# Embedded_System_Top.net
KiCad netlist of a schematic drawn in Altium Designer
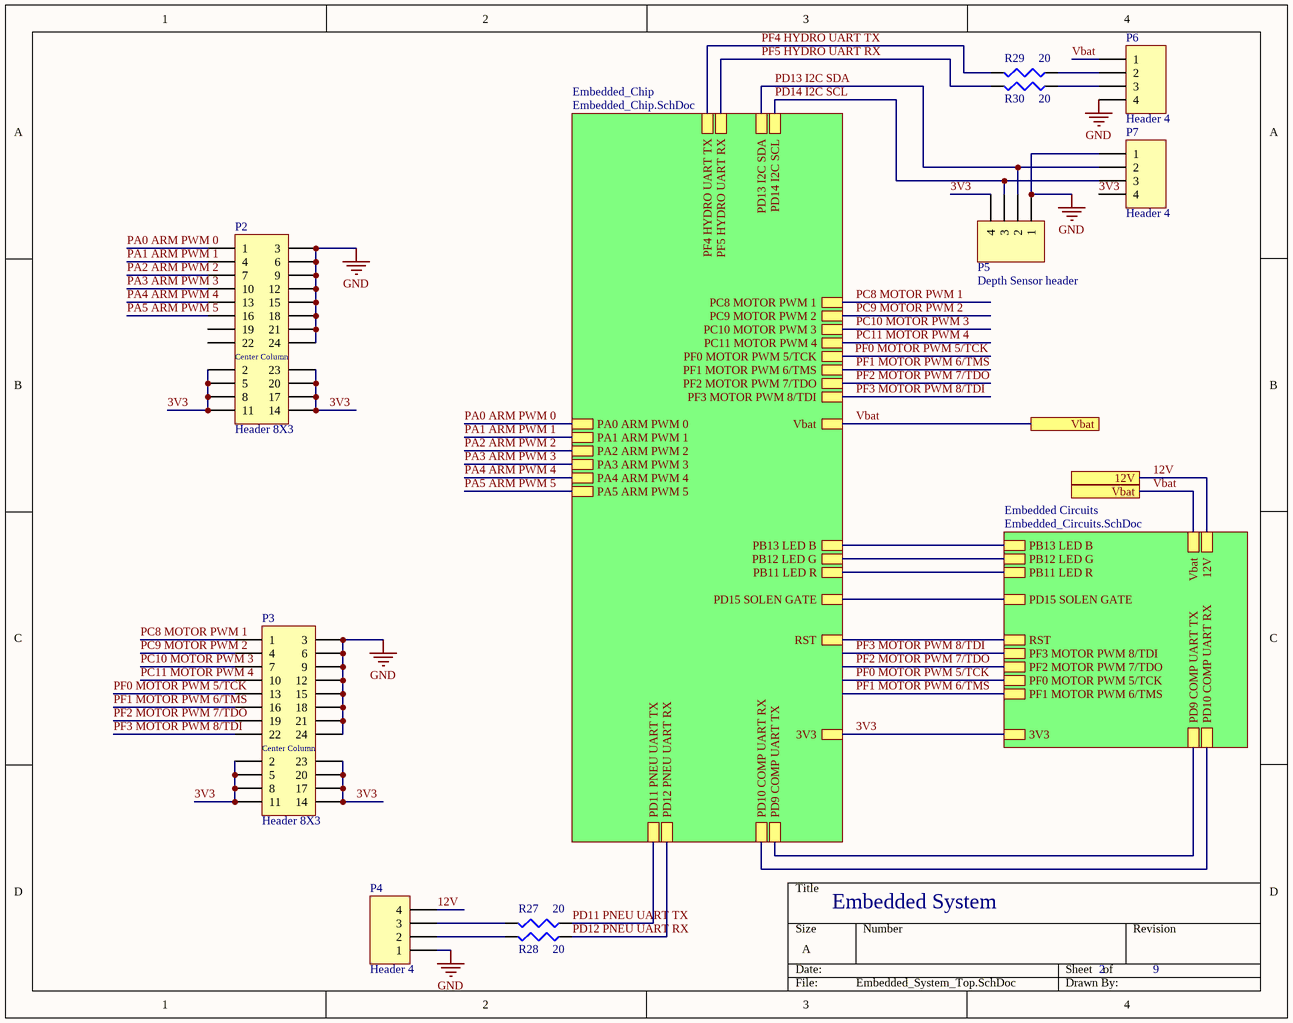
[diagram p0: Embedded_System_Top.SchDoc]

(export (version "E")
  (design (tool "Eeschema 10.0.6"))
  (components
    (comp (ref "P2")
      (value "Header 8X3")
      (footprint "Header 8X3")
      (description "Connector Header Through Hole 24 position 0.079\" (2.00mm)")
      (libsource (lib "Power_Embedded_Board_Library") (part "Header 8X3 (2mm)"))
    )
    (comp (ref "P3")
      (value "Header 8X3")
      (footprint "Header 8X3")
      (description "Connector Header Through Hole 24 position 0.079\" (2.00mm)")
      (libsource (lib "Power_Embedded_Board_Library") (part "Header 8X3 (2mm)"))
    )
    (comp (ref "P4")
      (value "Header 4")
      (footprint "Header 1x4")
      (description "Header, 4-Pin")
      (fields (field (name "PUBLISHER") "Altium Limited"))
      (libsource (lib "") (part "Header 4_2"))
    )
    (comp (ref "P5")
      (value "Depth Sensor header")
      (footprint "DF13-4P-1.25DSA")
      (description "Header, 4-Pin")
      (fields (field (name "PUBLISHER") "Altium Limited"))
      (libsource (lib "") (part "Header 4_1"))
    )
    (comp (ref "P6")
      (value "Header 4")
      (footprint "Header 1x4")
      (description "Header, 4-Pin")
      (fields (field (name "PUBLISHER") "Altium Limited"))
      (libsource (lib "Miscellaneous Connectors") (part "Header 4"))
    )
    (comp (ref "P7")
      (value "Header 4")
      (footprint "DF13-4P-1.25DSA")
      (description "Header, 4-Pin")
      (fields (field (name "PUBLISHER") "Altium Limited"))
      (libsource (lib "Miscellaneous Connectors") (part "Header 4"))
    )
    (comp (ref "R27")
      (value "20")
      (footprint "J1-0603")
      (description "Resistor")
      (fields (field (name "Comment") "Res3") (field (name "PUBLISHER") "Altium Limited"))
      (libsource (lib "Miscellaneous Devices") (part "Res3"))
    )
    (comp (ref "R28")
      (value "20")
      (footprint "J1-0603")
      (description "Resistor")
      (fields (field (name "Comment") "Res3") (field (name "PUBLISHER") "Altium Limited"))
      (libsource (lib "Miscellaneous Devices") (part "Res3"))
    )
    (comp (ref "R29")
      (value "20")
      (footprint "J1-0603")
      (description "Resistor")
      (fields (field (name "Comment") "Res3") (field (name "PUBLISHER") "Altium Limited"))
      (libsource (lib "Miscellaneous Devices") (part "Res3"))
    )
    (comp (ref "R30")
      (value "20")
      (footprint "J1-0603")
      (description "Resistor")
      (fields (field (name "Comment") "Res3") (field (name "PUBLISHER") "Altium Limited"))
      (libsource (lib "Miscellaneous Devices") (part "Res3"))
    )
  )
  (nets
    (net (code "1") (name "/3V3") (class "Default")
      (node (ref "P2") (pin "11") (pinfunction "11_11") (pintype "passive"))
      (node (ref "P2") (pin "14") (pinfunction "14_14") (pintype "passive"))
      (node (ref "P2") (pin "17") (pinfunction "17_17") (pintype "passive"))
      (node (ref "P2") (pin "2") (pinfunction "2_2") (pintype "passive"))
      (node (ref "P2") (pin "20") (pinfunction "20_20") (pintype "passive"))
      (node (ref "P2") (pin "23") (pinfunction "23_23") (pintype "passive"))
      (node (ref "P2") (pin "5") (pinfunction "5_5") (pintype "passive"))
      (node (ref "P2") (pin "8") (pinfunction "8_8") (pintype "passive"))
      (node (ref "P3") (pin "11") (pinfunction "11_11") (pintype "passive"))
      (node (ref "P3") (pin "14") (pinfunction "14_14") (pintype "passive"))
      (node (ref "P3") (pin "17") (pinfunction "17_17") (pintype "passive"))
      (node (ref "P3") (pin "2") (pinfunction "2_2") (pintype "passive"))
      (node (ref "P3") (pin "20") (pinfunction "20_20") (pintype "passive"))
      (node (ref "P3") (pin "23") (pinfunction "23_23") (pintype "passive"))
      (node (ref "P3") (pin "5") (pinfunction "5_5") (pintype "passive"))
      (node (ref "P3") (pin "8") (pinfunction "8_8") (pintype "passive"))
      (node (ref "P5") (pin "4") (pinfunction "4_4") (pintype "passive"))
      (node (ref "P7") (pin "4") (pinfunction "4_4") (pintype "passive"))
    )
    (net (code "2") (name "/12V") (class "Default")
      (node (ref "P4") (pin "4") (pinfunction "4_4") (pintype "passive"))
    )
    (net (code "3") (name "/PA0 ARM PWM 0") (class "Default")
      (node (ref "P2") (pin "1") (pinfunction "1_1") (pintype "passive"))
    )
    (net (code "4") (name "/PA1 ARM PWM 1") (class "Default")
      (node (ref "P2") (pin "4") (pinfunction "4_4") (pintype "passive"))
    )
    (net (code "5") (name "/PA2 ARM PWM 2") (class "Default")
      (node (ref "P2") (pin "7") (pinfunction "7_7") (pintype "passive"))
    )
    (net (code "6") (name "/PA3 ARM PWM 3") (class "Default")
      (node (ref "P2") (pin "10") (pinfunction "10_10") (pintype "passive"))
    )
    (net (code "7") (name "/PA4 ARM PWM 4") (class "Default")
      (node (ref "P2") (pin "13") (pinfunction "13_13") (pintype "passive"))
    )
    (net (code "8") (name "/PA5 ARM PWM 5") (class "Default")
      (node (ref "P2") (pin "16") (pinfunction "16_16") (pintype "passive"))
    )
    (net (code "12") (name "/PC8 MOTOR PWM 1") (class "Default")
      (node (ref "P3") (pin "1") (pinfunction "1_1") (pintype "passive"))
    )
    (net (code "13") (name "/PC9 MOTOR PWM 2") (class "Default")
      (node (ref "P3") (pin "4") (pinfunction "4_4") (pintype "passive"))
    )
    (net (code "14") (name "/PC10 MOTOR PWM 3") (class "Default")
      (node (ref "P3") (pin "7") (pinfunction "7_7") (pintype "passive"))
    )
    (net (code "15") (name "/PC11 MOTOR PWM 4") (class "Default")
      (node (ref "P3") (pin "10") (pinfunction "10_10") (pintype "passive"))
    )
    (net (code "18") (name "/PD11 PNEU UART TX") (class "Default")
      (node (ref "R27") (pin "1") (pinfunction "1_1") (pintype "passive"))
    )
    (net (code "19") (name "/PD12 PNEU UART RX") (class "Default")
      (node (ref "R28") (pin "1") (pinfunction "1_1") (pintype "passive"))
    )
    (net (code "20") (name "/PD13 I2C SDA") (class "Default")
      (node (ref "P5") (pin "2") (pinfunction "2_2") (pintype "passive"))
      (node (ref "P7") (pin "2") (pinfunction "2_2") (pintype "passive"))
    )
    (net (code "21") (name "/PD14 I2C SCL") (class "Default")
      (node (ref "P5") (pin "3") (pinfunction "3_3") (pintype "passive"))
      (node (ref "P7") (pin "3") (pinfunction "3_3") (pintype "passive"))
    )
    (net (code "23") (name "/PF0 MOTOR PWM 5{slash}TCK") (class "Default")
      (node (ref "P3") (pin "13") (pinfunction "13_13") (pintype "passive"))
    )
    (net (code "24") (name "/PF1 MOTOR PWM 6{slash}TMS") (class "Default")
      (node (ref "P3") (pin "16") (pinfunction "16_16") (pintype "passive"))
    )
    (net (code "25") (name "/PF2 MOTOR PWM 7{slash}TDO") (class "Default")
      (node (ref "P3") (pin "19") (pinfunction "19_19") (pintype "passive"))
    )
    (net (code "26") (name "/PF3 MOTOR PWM 8{slash}TDI") (class "Default")
      (node (ref "P3") (pin "22") (pinfunction "22_22") (pintype "passive"))
    )
    (net (code "27") (name "/PF4 HYDRO UART TX") (class "Default")
      (node (ref "R29") (pin "2") (pinfunction "2_2") (pintype "passive"))
    )
    (net (code "28") (name "/PF5 HYDRO UART RX") (class "Default")
      (node (ref "R30") (pin "2") (pinfunction "2_2") (pintype "passive"))
    )
    (net (code "30") (name "/Vbat") (class "Default")
      (node (ref "P6") (pin "1") (pinfunction "1_1") (pintype "passive"))
    )
    (net (code "31") (name "GND") (class "Default")
      (node (ref "P2") (pin "12") (pinfunction "12_12") (pintype "passive"))
      (node (ref "P2") (pin "15") (pinfunction "15_15") (pintype "passive"))
      (node (ref "P2") (pin "18") (pinfunction "18_18") (pintype "passive"))
      (node (ref "P2") (pin "21") (pinfunction "21_21") (pintype "passive"))
      (node (ref "P2") (pin "24") (pinfunction "24_24") (pintype "passive"))
      (node (ref "P2") (pin "3") (pinfunction "3_3") (pintype "passive"))
      (node (ref "P2") (pin "6") (pinfunction "6_6") (pintype "passive"))
      (node (ref "P2") (pin "9") (pinfunction "9_9") (pintype "passive"))
      (node (ref "P3") (pin "12") (pinfunction "12_12") (pintype "passive"))
      (node (ref "P3") (pin "15") (pinfunction "15_15") (pintype "passive"))
      (node (ref "P3") (pin "18") (pinfunction "18_18") (pintype "passive"))
      (node (ref "P3") (pin "21") (pinfunction "21_21") (pintype "passive"))
      (node (ref "P3") (pin "24") (pinfunction "24_24") (pintype "passive"))
      (node (ref "P3") (pin "3") (pinfunction "3_3") (pintype "passive"))
      (node (ref "P3") (pin "6") (pinfunction "6_6") (pintype "passive"))
      (node (ref "P3") (pin "9") (pinfunction "9_9") (pintype "passive"))
      (node (ref "P4") (pin "1") (pinfunction "1_1") (pintype "passive"))
      (node (ref "P5") (pin "1") (pinfunction "1_1") (pintype "passive"))
      (node (ref "P6") (pin "4") (pinfunction "4_4") (pintype "passive"))
      (node (ref "P7") (pin "1") (pinfunction "1_1") (pintype "passive"))
    )
    (net (code "32") (name "Net-(P4-Pad2)") (class "Default")
      (node (ref "P4") (pin "2") (pinfunction "2_2") (pintype "passive"))
      (node (ref "R28") (pin "2") (pinfunction "2_2") (pintype "passive"))
    )
    (net (code "33") (name "Net-(P4-Pad3)") (class "Default")
      (node (ref "P4") (pin "3") (pinfunction "3_3") (pintype "passive"))
      (node (ref "R27") (pin "2") (pinfunction "2_2") (pintype "passive"))
    )
    (net (code "34") (name "Net-(P6-Pad2)") (class "Default")
      (node (ref "P6") (pin "2") (pinfunction "2_2") (pintype "passive"))
      (node (ref "R29") (pin "1") (pinfunction "1_1") (pintype "passive"))
    )
    (net (code "35") (name "Net-(P6-Pad3)") (class "Default")
      (node (ref "P6") (pin "3") (pinfunction "3_3") (pintype "passive"))
      (node (ref "R30") (pin "1") (pinfunction "1_1") (pintype "passive"))
    )
    (net (code "36") (name "unconnected-(P2-Pad19)") (class "Default")
      (node (ref "P2") (pin "19") (pinfunction "19_19") (pintype "passive"))
    )
    (net (code "37") (name "unconnected-(P2-Pad22)") (class "Default")
      (node (ref "P2") (pin "22") (pinfunction "22_22") (pintype "passive"))
    )
  )
)
